# DC-DC_StepDown_in_Box_45x30x15.net
KiCad netlist of a schematic drawn in Altium Designer
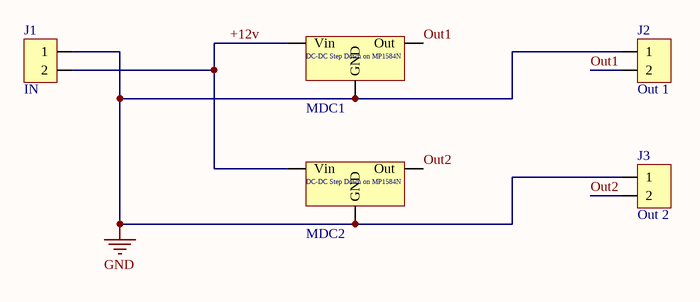
[diagram p0: DC-DC StepDown in Box 45x30x15 (moto).SchDoc]

(export (version "E")
  (design (tool "Eeschema 10.0.6"))
  (components
    (comp (ref "J1")
      (value "IN")
      (footprint "Connector:Molex Micro-Fit 3.0 - 2 pin D R")
      (description "Horisontal, Dbl line, Male - 3mm")
      (fields (field (name "PART NUMBER") "430450200"))
      (libsource (lib "Connector") (part "Micro-Fit 2R (1x2)"))
    )
    (comp (ref "J2")
      (value "Out 1")
      (footprint "Connector:Molex Micro-Fit 3.0 - 2 pin D R")
      (description "Horisontal, Dbl line, Male - 3mm")
      (fields (field (name "PART NUMBER") "430450200"))
      (libsource (lib "") (part "Micro-Fit 2R (1x2)_1"))
    )
    (comp (ref "J3")
      (value "Out 2")
      (footprint "Connector:Molex Micro-Fit 3.0 - 2 pin D R")
      (description "Horisontal, Dbl line, Male - 3mm")
      (fields (field (name "PART NUMBER") "430450200"))
      (libsource (lib "") (part "Micro-Fit 2R (1x2)_1"))
    )
    (comp (ref "MDC1")
      (value "DC-DC")
      (footprint "Modules:DC-DC_MP1584N")
      (description "DC-DC StepDown")
      (libsource (lib "Modules") (part "DC-DC MP1584N"))
    )
    (comp (ref "MDC2")
      (value "DC-DC")
      (footprint "Modules:DC-DC_MP1584N")
      (description "DC-DC StepDown")
      (libsource (lib "Modules") (part "DC-DC MP1584N"))
    )
  )
  (nets
    (net (code "1") (name "/+12v") (class "Default")
      (node (ref "J1") (pin "2") (pinfunction "2_2") (pintype "passive"))
      (node (ref "MDC1") (pin "IN") (pinfunction "Vin_IN") (pintype "passive"))
      (node (ref "MDC2") (pin "IN") (pinfunction "Vin_IN") (pintype "passive"))
    )
    (net (code "2") (name "/Out1") (class "Default")
      (node (ref "J2") (pin "2") (pinfunction "2_2") (pintype "passive"))
      (node (ref "MDC1") (pin "OUT") (pinfunction "Out_OUT") (pintype "passive"))
    )
    (net (code "3") (name "/Out2") (class "Default")
      (node (ref "J3") (pin "2") (pinfunction "2_2") (pintype "passive"))
      (node (ref "MDC2") (pin "OUT") (pinfunction "Out_OUT") (pintype "passive"))
    )
    (net (code "4") (name "GND") (class "Default")
      (node (ref "J1") (pin "1") (pinfunction "1_1") (pintype "passive"))
      (node (ref "J2") (pin "1") (pinfunction "1_1") (pintype "passive"))
      (node (ref "J3") (pin "1") (pinfunction "1_1") (pintype "passive"))
      (node (ref "MDC1") (pin "GND") (pinfunction "GND_GND") (pintype "passive"))
      (node (ref "MDC2") (pin "GND") (pinfunction "GND_GND") (pintype "passive"))
    )
  )
)
